# dcdc.net
KiCad netlist of a schematic drawn in Altium Designer
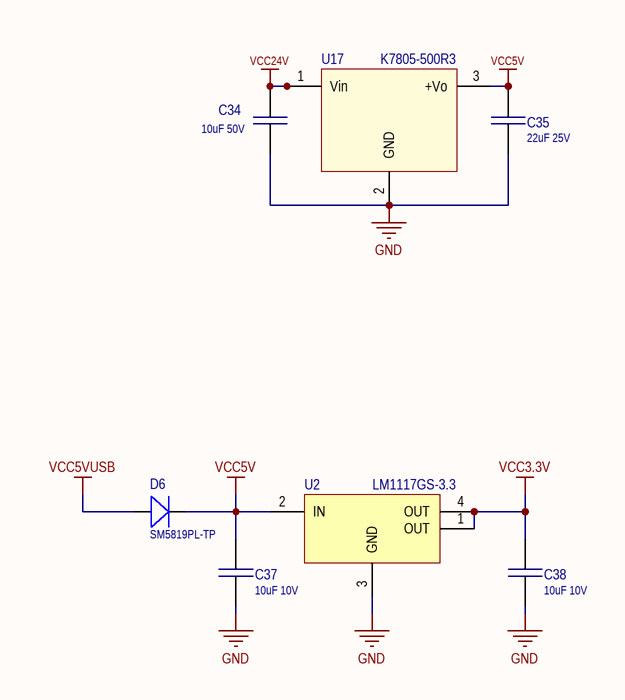
[diagram p0: dcdc.schdoc]

(export (version "E")
  (design (tool "Eeschema 10.0.6"))
  (components
    (comp (ref "C34")
      (value "10uF 50V")
      (footprint "C_1206")
      (description "Capacitor")
      (fields (field (name "PART") "CC1206KKX5R9BB106") (field (name "ALTERNATIVE PART") "CL31A106KBHNNNE"))
      (libsource (lib "capacitors") (part "C1206"))
    )
    (comp (ref "C35")
      (value "22uF 25V")
      (footprint "C_1206")
      (description "Capacitor")
      (fields (field (name "PART") "CC1206KKX5R8BB226") (field (name "ALTERNATIVE PART") "CL31A226KAHNNNE"))
      (libsource (lib "capacitors") (part "C1206"))
    )
    (comp (ref "C37")
      (value "10uF 10V")
      (footprint "C_0805")
      (description "Capacitor")
      (fields (field (name "PART") "CC0805KKX5R6BB106") (field (name "JLCPCB PART") "C89832"))
      (libsource (lib "capacitors") (part "C0805"))
    )
    (comp (ref "C38")
      (value "10uF 10V")
      (footprint "C_0805")
      (description "Capacitor")
      (fields (field (name "PART") "CC0805KKX5R6BB106") (field (name "JLCPCB PART") "C89832"))
      (libsource (lib "capacitors") (part "C0805"))
    )
    (comp (ref "D6")
      (value "SM5819PL-TP")
      (footprint "SOD-123")
      (description "Diode")
      (fields (field (name "JLCPCB PART") "C19992592"))
      (libsource (lib "AX_Altium_v2.3") (part "D_SOD123"))
    )
    (comp (ref "U2")
      (value "LM1117GS-3.3")
      (footprint "SOT 223")
      (fields (field (name "JLCPCB PART") "C411821"))
      (libsource (lib "dcdc_ldo_ref") (part "LDO 3.3v"))
    )
    (comp (ref "U17")
      (value "K7805-500R3")
      (footprint "K7805500R3")
      (description "Non-isolated dc-dc")
      (fields (field (name "JLCPCB PART") "C19188491"))
      (libsource (lib "dcdc_ldo_ref") (part "K78xx-500R3"))
    )
  )
  (nets
    (net (code "1") (name "GND") (class "Default")
      (node (ref "C34") (pin "2") (pinfunction "2_2") (pintype "passive"))
      (node (ref "C35") (pin "1") (pinfunction "1_1") (pintype "passive"))
      (node (ref "C37") (pin "1") (pinfunction "1_1") (pintype "passive"))
      (node (ref "C38") (pin "1") (pinfunction "1_1") (pintype "passive"))
      (node (ref "U17") (pin "2") (pinfunction "GND_2") (pintype "passive"))
      (node (ref "U2") (pin "3") (pinfunction "GND_3") (pintype "passive"))
    )
    (net (code "2") (name "VCC3.3V") (class "Default")
      (node (ref "C38") (pin "2") (pinfunction "2_2") (pintype "passive"))
      (node (ref "U2") (pin "1") (pinfunction "OUT_1") (pintype "passive"))
      (node (ref "U2") (pin "4") (pinfunction "OUT_4") (pintype "passive"))
    )
    (net (code "3") (name "VCC5V") (class "Default")
      (node (ref "C35") (pin "2") (pinfunction "2_2") (pintype "passive"))
      (node (ref "C37") (pin "2") (pinfunction "2_2") (pintype "passive"))
      (node (ref "D6") (pin "2") (pinfunction "K_2") (pintype "passive"))
      (node (ref "U17") (pin "3") (pinfunction "+Vo_3") (pintype "passive"))
      (node (ref "U2") (pin "2") (pinfunction "IN_2") (pintype "passive"))
    )
    (net (code "4") (name "VCC5VUSB") (class "Default")
      (node (ref "D6") (pin "1") (pinfunction "A_1") (pintype "passive"))
    )
    (net (code "5") (name "VCC24V") (class "Default")
      (node (ref "C34") (pin "1") (pinfunction "1_1") (pintype "passive"))
      (node (ref "U17") (pin "1") (pinfunction "Vin_1") (pintype "passive"))
    )
  )
)
